# 10_-_GMAC0.net
KiCad netlist of a schematic drawn in Altium Designer
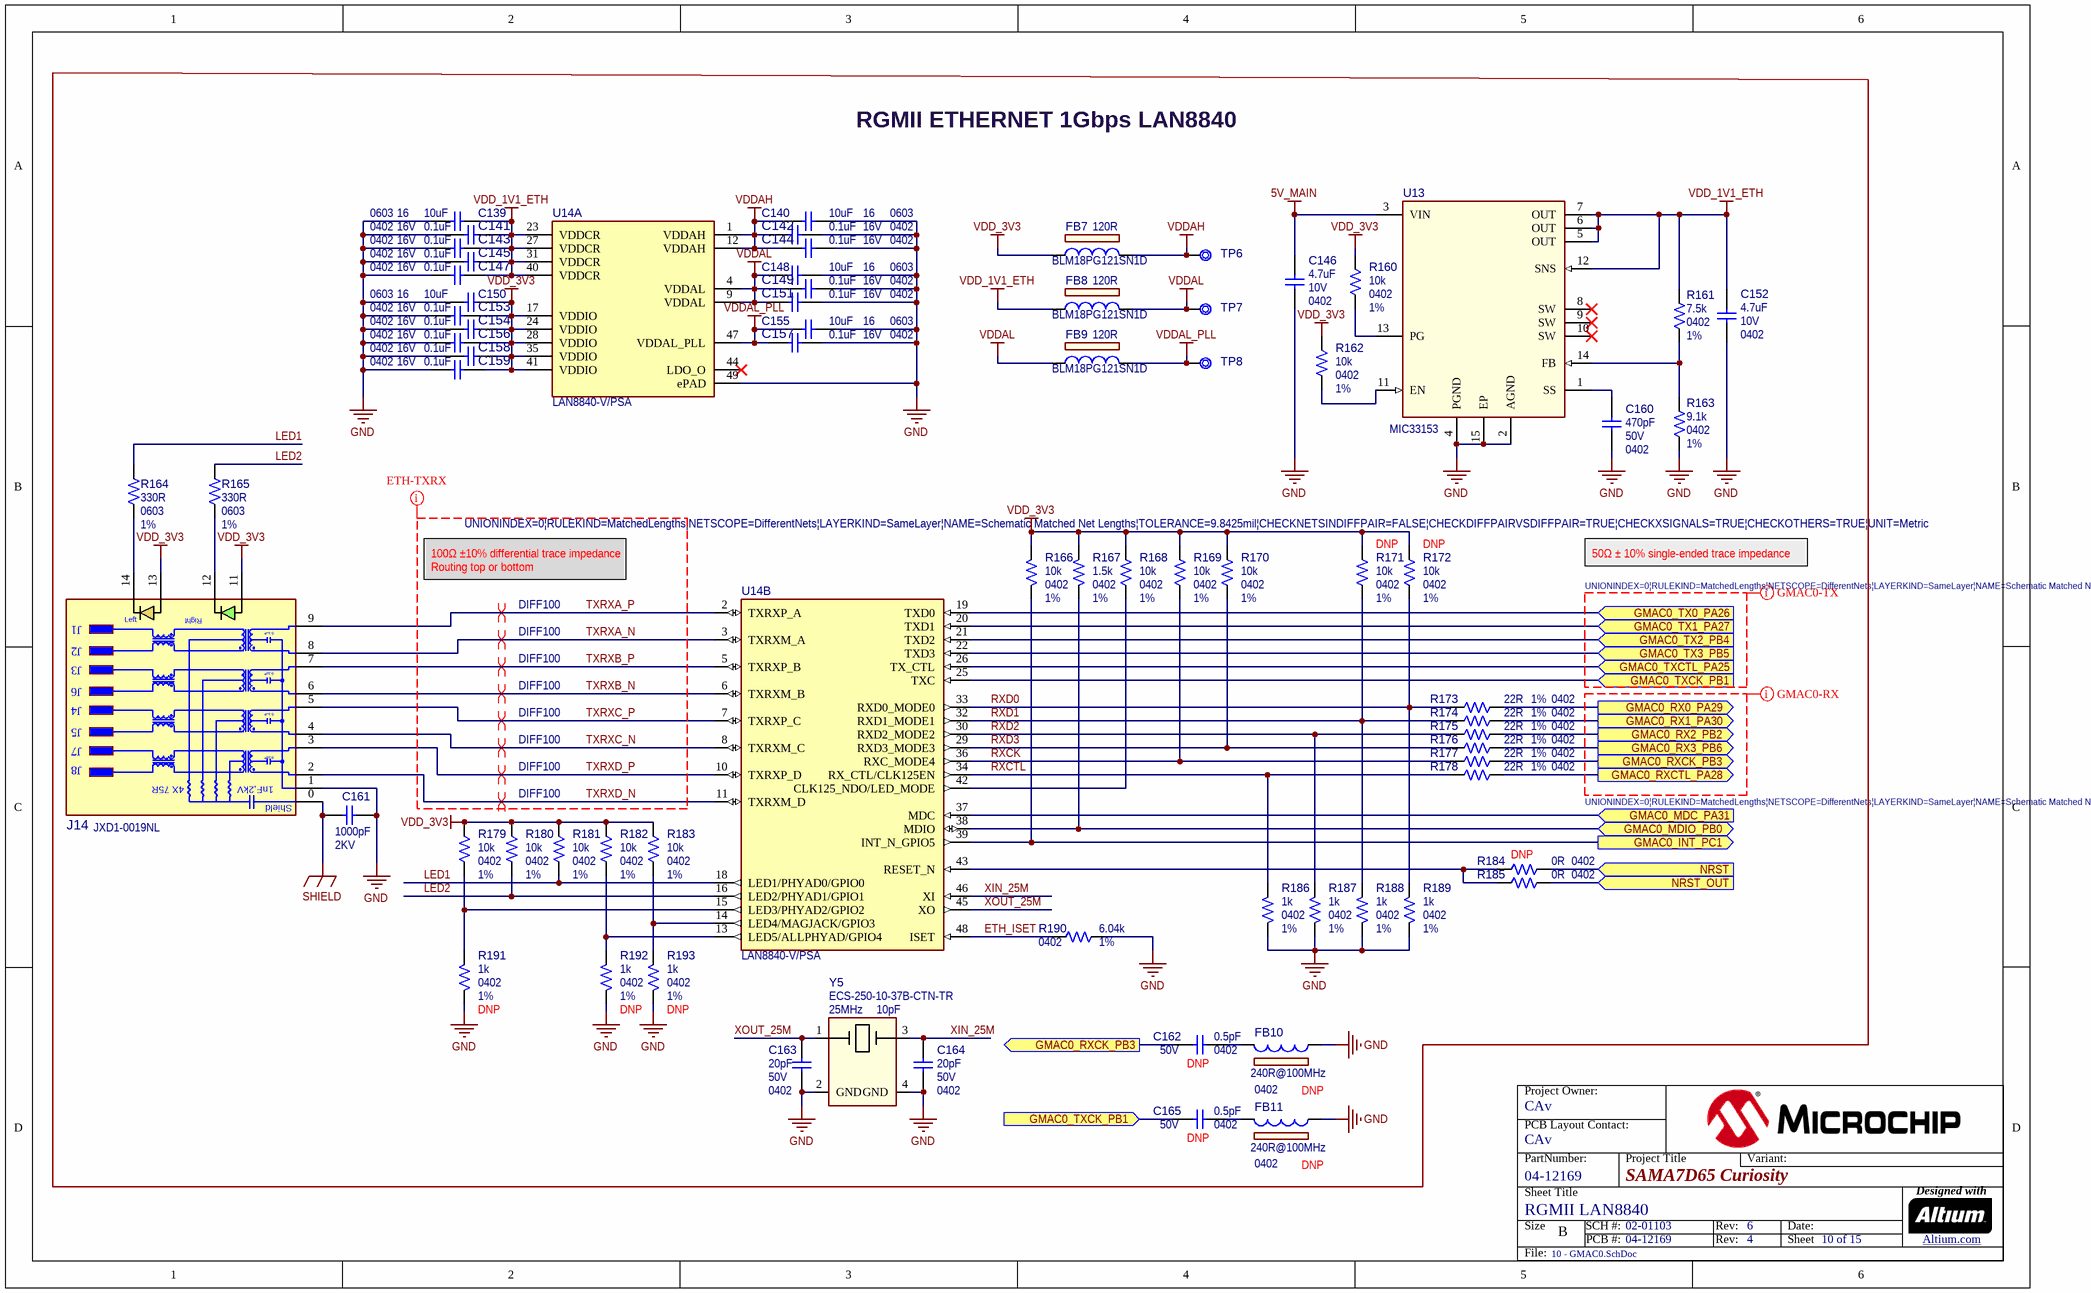
[diagram p0: 10 - GMAC0.SchDoc]

(export (version "E")
  (design (tool "Eeschema 10.0.6"))
  (components
    (comp (ref "C139")
      (value "10uF")
      (footprint "CAP_C_0603")
      (fields
        (field (name "VOLTAGE") "16")
        (field (name "PACKAGE") "0603")
        (field (name "TOLERANCE") "10%")
        (field (name "Comment") "Capacitor NP")
        (field (name "OWNER") "Sam Charles")
      )
      (libsource (lib "MCHP-CDB") (part "Capacitor NP"))
    )
    (comp (ref "C140")
      (value "10uF")
      (footprint "CAP_C_0603")
      (fields
        (field (name "VOLTAGE") "16")
        (field (name "PACKAGE") "0603")
        (field (name "TOLERANCE") "10%")
        (field (name "Comment") "Capacitor NP")
        (field (name "OWNER") "Sam Charles")
      )
      (libsource (lib "MCHP-CDB") (part "Capacitor NP"))
    )
    (comp (ref "C141")
      (value "0.1uF")
      (footprint "CAP_C_0402")
      (fields
        (field (name "VOLTAGE") "16V")
        (field (name "PACKAGE") "0402")
        (field (name "TOLERANCE") "10%")
        (field (name "Comment") "Capacitor NP")
        (field (name "OWNER") "Sompoch Loboonlert")
      )
      (libsource (lib "MCHP-CDB") (part "Capacitor NP"))
    )
    (comp (ref "C142")
      (value "0.1uF")
      (footprint "CAP_C_0402")
      (fields
        (field (name "VOLTAGE") "16V")
        (field (name "PACKAGE") "0402")
        (field (name "TOLERANCE") "10%")
        (field (name "Comment") "Capacitor NP")
        (field (name "OWNER") "Sompoch Loboonlert")
      )
      (libsource (lib "MCHP-CDB") (part "Capacitor NP"))
    )
    (comp (ref "C143")
      (value "0.1uF")
      (footprint "CAP_C_0402")
      (fields
        (field (name "VOLTAGE") "16V")
        (field (name "PACKAGE") "0402")
        (field (name "TOLERANCE") "10%")
        (field (name "Comment") "Capacitor NP")
        (field (name "OWNER") "Sompoch Loboonlert")
      )
      (libsource (lib "MCHP-CDB") (part "Capacitor NP"))
    )
    (comp (ref "C144")
      (value "0.1uF")
      (footprint "CAP_C_0402")
      (fields
        (field (name "VOLTAGE") "16V")
        (field (name "PACKAGE") "0402")
        (field (name "TOLERANCE") "10%")
        (field (name "Comment") "Capacitor NP")
        (field (name "OWNER") "Sompoch Loboonlert")
      )
      (libsource (lib "MCHP-CDB") (part "Capacitor NP"))
    )
    (comp (ref "C145")
      (value "0.1uF")
      (footprint "CAP_C_0402")
      (fields
        (field (name "VOLTAGE") "16V")
        (field (name "PACKAGE") "0402")
        (field (name "TOLERANCE") "10%")
        (field (name "Comment") "Capacitor NP")
        (field (name "OWNER") "Sompoch Loboonlert")
      )
      (libsource (lib "MCHP-CDB") (part "Capacitor NP"))
    )
    (comp (ref "C146")
      (value "4.7uF")
      (footprint "CAP_C_0402")
      (description "Capacitor")
      (fields
        (field (name "VOLTAGE") "10V")
        (field (name "PACKAGE") "0402")
        (field (name "TOLERANCE") "10%")
        (field (name "Comment") "Capacitor NP")
        (field (name "OWNER") "Jesus Aviles")
      )
      (libsource (lib "") (part "Capacitor NP_1"))
    )
    (comp (ref "C147")
      (value "0.1uF")
      (footprint "CAP_C_0402")
      (fields
        (field (name "VOLTAGE") "16V")
        (field (name "PACKAGE") "0402")
        (field (name "TOLERANCE") "10%")
        (field (name "Comment") "Capacitor NP")
        (field (name "OWNER") "Sompoch Loboonlert")
      )
      (libsource (lib "MCHP-CDB") (part "Capacitor NP"))
    )
    (comp (ref "C148")
      (value "10uF")
      (footprint "CAP_C_0603")
      (fields
        (field (name "VOLTAGE") "16")
        (field (name "PACKAGE") "0603")
        (field (name "TOLERANCE") "10%")
        (field (name "Comment") "Capacitor NP")
        (field (name "OWNER") "Sam Charles")
      )
      (libsource (lib "MCHP-CDB") (part "Capacitor NP"))
    )
    (comp (ref "C149")
      (value "0.1uF")
      (footprint "CAP_C_0402")
      (fields
        (field (name "VOLTAGE") "16V")
        (field (name "PACKAGE") "0402")
        (field (name "TOLERANCE") "10%")
        (field (name "Comment") "Capacitor NP")
        (field (name "OWNER") "Sompoch Loboonlert")
      )
      (libsource (lib "MCHP-CDB") (part "Capacitor NP"))
    )
    (comp (ref "C150")
      (value "10uF")
      (footprint "CAP_C_0603")
      (fields
        (field (name "VOLTAGE") "16")
        (field (name "PACKAGE") "0603")
        (field (name "TOLERANCE") "10%")
        (field (name "Comment") "Capacitor NP")
        (field (name "OWNER") "Sam Charles")
      )
      (libsource (lib "MCHP-CDB") (part "Capacitor NP"))
    )
    (comp (ref "C151")
      (value "0.1uF")
      (footprint "CAP_C_0402")
      (fields
        (field (name "VOLTAGE") "16V")
        (field (name "PACKAGE") "0402")
        (field (name "TOLERANCE") "10%")
        (field (name "Comment") "Capacitor NP")
        (field (name "OWNER") "Sompoch Loboonlert")
      )
      (libsource (lib "MCHP-CDB") (part "Capacitor NP"))
    )
    (comp (ref "C152")
      (value "4.7uF")
      (footprint "CAP_C_0402")
      (description "Capacitor")
      (fields
        (field (name "VOLTAGE") "10V")
        (field (name "PACKAGE") "0402")
        (field (name "TOLERANCE") "10%")
        (field (name "Comment") "Capacitor NP")
        (field (name "OWNER") "Jesus Aviles")
      )
      (libsource (lib "") (part "Capacitor NP_1"))
    )
    (comp (ref "C153")
      (value "0.1uF")
      (footprint "CAP_C_0402")
      (fields
        (field (name "VOLTAGE") "16V")
        (field (name "PACKAGE") "0402")
        (field (name "TOLERANCE") "10%")
        (field (name "Comment") "Capacitor NP")
        (field (name "OWNER") "Sompoch Loboonlert")
      )
      (libsource (lib "MCHP-CDB") (part "Capacitor NP"))
    )
    (comp (ref "C154")
      (value "0.1uF")
      (footprint "CAP_C_0402")
      (fields
        (field (name "VOLTAGE") "16V")
        (field (name "PACKAGE") "0402")
        (field (name "TOLERANCE") "10%")
        (field (name "Comment") "Capacitor NP")
        (field (name "OWNER") "Sompoch Loboonlert")
      )
      (libsource (lib "MCHP-CDB") (part "Capacitor NP"))
    )
    (comp (ref "C155")
      (value "10uF")
      (footprint "CAP_C_0603")
      (fields
        (field (name "VOLTAGE") "16")
        (field (name "PACKAGE") "0603")
        (field (name "TOLERANCE") "10%")
        (field (name "Comment") "Capacitor NP")
        (field (name "OWNER") "Sam Charles")
      )
      (libsource (lib "MCHP-CDB") (part "Capacitor NP"))
    )
    (comp (ref "C156")
      (value "0.1uF")
      (footprint "CAP_C_0402")
      (fields
        (field (name "VOLTAGE") "16V")
        (field (name "PACKAGE") "0402")
        (field (name "TOLERANCE") "10%")
        (field (name "Comment") "Capacitor NP")
        (field (name "OWNER") "Sompoch Loboonlert")
      )
      (libsource (lib "MCHP-CDB") (part "Capacitor NP"))
    )
    (comp (ref "C157")
      (value "0.1uF")
      (footprint "CAP_C_0402")
      (fields
        (field (name "VOLTAGE") "16V")
        (field (name "PACKAGE") "0402")
        (field (name "TOLERANCE") "10%")
        (field (name "Comment") "Capacitor NP")
        (field (name "OWNER") "Sompoch Loboonlert")
      )
      (libsource (lib "MCHP-CDB") (part "Capacitor NP"))
    )
    (comp (ref "C158")
      (value "0.1uF")
      (footprint "CAP_C_0402")
      (fields
        (field (name "VOLTAGE") "16V")
        (field (name "PACKAGE") "0402")
        (field (name "TOLERANCE") "10%")
        (field (name "Comment") "Capacitor NP")
        (field (name "OWNER") "Sompoch Loboonlert")
      )
      (libsource (lib "MCHP-CDB") (part "Capacitor NP"))
    )
    (comp (ref "C159")
      (value "0.1uF")
      (footprint "CAP_C_0402")
      (fields
        (field (name "VOLTAGE") "16V")
        (field (name "PACKAGE") "0402")
        (field (name "TOLERANCE") "10%")
        (field (name "Comment") "Capacitor NP")
        (field (name "OWNER") "Sompoch Loboonlert")
      )
      (libsource (lib "MCHP-CDB") (part "Capacitor NP"))
    )
    (comp (ref "C160")
      (value "470pF")
      (footprint "CAP_C_0402")
      (fields
        (field (name "VOLTAGE") "50V")
        (field (name "PACKAGE") "0402")
        (field (name "TOLERANCE") "5%")
        (field (name "Comment") "Capacitor NP")
        (field (name "OWNER") "Duane Burt")
      )
      (libsource (lib "MCHP-CDB") (part "Capacitor NP"))
    )
    (comp (ref "C161")
      (value "1000pF")
      (footprint "CAP_C_1206")
      (fields
        (field (name "VOLTAGE") "2KV")
        (field (name "Comment") "Capacitor NP")
        (field (name "OWNER") "Jamus Griego")
      )
      (libsource (lib "MCHP-CDB") (part "Capacitor NP"))
    )
    (comp (ref "C162")
      (value "0.5pF")
      (footprint "CAP_C_0402")
      (fields
        (field (name "VOLTAGE") "50V")
        (field (name "PACKAGE") "0402")
        (field (name "TOLERANCE") "0.25pF")
        (field (name "POPULATED") "DNP")
        (field (name "Comment") "Capacitor NP")
      )
      (libsource (lib "MCHP-CDB") (part "Capacitor NP"))
    )
    (comp (ref "C163")
      (value "20pF")
      (footprint "CAP_C_0402")
      (fields
        (field (name "VOLTAGE") "50V")
        (field (name "PACKAGE") "0402")
        (field (name "TOLERANCE") "5%")
        (field (name "Comment") "Capacitor NP")
      )
      (libsource (lib "MCHP-CDB") (part "Capacitor NP"))
    )
    (comp (ref "C164")
      (value "20pF")
      (footprint "CAP_C_0402")
      (fields
        (field (name "VOLTAGE") "50V")
        (field (name "PACKAGE") "0402")
        (field (name "TOLERANCE") "5%")
        (field (name "Comment") "Capacitor NP")
      )
      (libsource (lib "MCHP-CDB") (part "Capacitor NP"))
    )
    (comp (ref "C165")
      (value "0.5pF")
      (footprint "CAP_C_0402")
      (fields
        (field (name "VOLTAGE") "50V")
        (field (name "PACKAGE") "0402")
        (field (name "TOLERANCE") "0.25pF")
        (field (name "POPULATED") "DNP")
        (field (name "Comment") "Capacitor NP")
      )
      (libsource (lib "MCHP-CDB") (part "Capacitor NP"))
    )
    (comp (ref "FB7")
      (value "120R")
      (footprint "IND_C_0603")
      (fields
        (field (name "MANUFACTURER PART NUMBER 1") "BLM18PG121SN1D")
        (field (name "Comment") "Ferrite Bead")
        (field (name "OWNER") "Petnarong Chaijaroong")
      )
      (libsource (lib "") (part "Ferrite Bead_1"))
    )
    (comp (ref "FB8")
      (value "120R")
      (footprint "IND_C_0603")
      (fields
        (field (name "MANUFACTURER PART NUMBER 1") "BLM18PG121SN1D")
        (field (name "Comment") "Ferrite Bead")
        (field (name "OWNER") "Petnarong Chaijaroong")
      )
      (libsource (lib "") (part "Ferrite Bead_1"))
    )
    (comp (ref "FB9")
      (value "120R")
      (footprint "IND_C_0603")
      (fields
        (field (name "MANUFACTURER PART NUMBER 1") "BLM18PG121SN1D")
        (field (name "Comment") "Ferrite Bead")
        (field (name "OWNER") "Petnarong Chaijaroong")
      )
      (libsource (lib "") (part "Ferrite Bead_1"))
    )
    (comp (ref "FB10")
      (value "240R@100MHz")
      (footprint "IND_C_0402")
      (fields
        (field (name "PACKAGE") "0402")
        (field (name "POPULATED") "DNP")
        (field (name "Comment") "Ferrite Bead")
        (field (name "OWNER") "Joerg Buehrer")
      )
      (libsource (lib "MCHP-CDB") (part "Ferrite Bead"))
    )
    (comp (ref "FB11")
      (value "240R@100MHz")
      (footprint "IND_C_0402")
      (fields
        (field (name "PACKAGE") "0402")
        (field (name "POPULATED") "DNP")
        (field (name "Comment") "Ferrite Bead")
        (field (name "OWNER") "Joerg Buehrer")
      )
      (libsource (lib "MCHP-CDB") (part "Ferrite Bead"))
    )
    (comp (ref "J14")
      (value "CON_RJ-45_TH_RA_PULSE_JXD1-0019NL")
      (footprint "CON_RJ-45_TH_RA_PULSE_JXD1-0019NL")
      (fields
        (field (name "MANUFACTURER PART NUMBER 1") "JXD1-0019NL")
        (field (name "OWNER") "Ciprian Abramov")
      )
      (libsource (lib "MCHP-CDB") (part "CON_RJ-45_TH_RA_PULSE_JXD1-0019NL"))
    )
    (comp (ref "R160")
      (value "10k")
      (footprint "RES_C_0402")
      (description "Resistor")
      (fields
        (field (name "PACKAGE") "0402")
        (field (name "TOLERANCE") "1%")
        (field (name "VOLTAGE") "50V")
        (field (name "POWER") "1/10W")
        (field (name "OWNER") "Brent Lanphear")
      )
      (libsource (lib "MCHP-CDB") (part "Resistor"))
    )
    (comp (ref "R161")
      (value "7.5k")
      (footprint "RES_C_0402")
      (description "Resistor")
      (fields
        (field (name "PACKAGE") "0402")
        (field (name "TOLERANCE") "1%")
        (field (name "POWER") "1/16W")
        (field (name "OWNER") "Stephen Humberd")
      )
      (libsource (lib "MCHP-CDB") (part "Resistor"))
    )
    (comp (ref "R162")
      (value "10k")
      (footprint "RES_C_0402")
      (description "Resistor")
      (fields
        (field (name "PACKAGE") "0402")
        (field (name "TOLERANCE") "1%")
        (field (name "VOLTAGE") "50V")
        (field (name "POWER") "1/10W")
        (field (name "OWNER") "Brent Lanphear")
      )
      (libsource (lib "MCHP-CDB") (part "Resistor"))
    )
    (comp (ref "R163")
      (value "9.1k")
      (footprint "RES_C_0402")
      (description "Resistor")
      (fields
        (field (name "PACKAGE") "0402")
        (field (name "TOLERANCE") "1%")
        (field (name "VOLTAGE") "50V")
        (field (name "POWER") "1/10W")
      )
      (libsource (lib "MCHP-CDB") (part "Resistor"))
    )
    (comp (ref "R164")
      (value "330R")
      (footprint "RES_C_0603")
      (description "Resistor")
      (fields
        (field (name "PACKAGE") "0603")
        (field (name "TOLERANCE") "1%")
        (field (name "VOLTAGE") "75V")
        (field (name "POWER") "1/10W")
      )
      (libsource (lib "MCHP-CDB") (part "Resistor"))
    )
    (comp (ref "R165")
      (value "330R")
      (footprint "RES_C_0603")
      (description "Resistor")
      (fields
        (field (name "PACKAGE") "0603")
        (field (name "TOLERANCE") "1%")
        (field (name "VOLTAGE") "75V")
        (field (name "POWER") "1/10W")
      )
      (libsource (lib "MCHP-CDB") (part "Resistor"))
    )
    (comp (ref "R166")
      (value "10k")
      (footprint "RES_C_0402")
      (description "Resistor")
      (fields
        (field (name "PACKAGE") "0402")
        (field (name "TOLERANCE") "1%")
        (field (name "VOLTAGE") "50V")
        (field (name "POWER") "1/10W")
        (field (name "OWNER") "Brent Lanphear")
      )
      (libsource (lib "MCHP-CDB") (part "Resistor"))
    )
    (comp (ref "R167")
      (value "1.5k")
      (footprint "RES_C_0402")
      (description "Resistor")
      (fields
        (field (name "PACKAGE") "0402")
        (field (name "TOLERANCE") "1%")
        (field (name "POWER") "1/10W")
        (field (name "OWNER") "Gabor Bihari")
      )
      (libsource (lib "MCHP-CDB") (part "Resistor"))
    )
    (comp (ref "R168")
      (value "10k")
      (footprint "RES_C_0402")
      (description "Resistor")
      (fields
        (field (name "PACKAGE") "0402")
        (field (name "TOLERANCE") "1%")
        (field (name "VOLTAGE") "50V")
        (field (name "POWER") "1/10W")
        (field (name "OWNER") "Brent Lanphear")
      )
      (libsource (lib "MCHP-CDB") (part "Resistor"))
    )
    (comp (ref "R169")
      (value "10k")
      (footprint "RES_C_0402")
      (description "Resistor")
      (fields
        (field (name "PACKAGE") "0402")
        (field (name "TOLERANCE") "1%")
        (field (name "VOLTAGE") "50V")
        (field (name "POWER") "1/10W")
        (field (name "OWNER") "Brent Lanphear")
      )
      (libsource (lib "MCHP-CDB") (part "Resistor"))
    )
    (comp (ref "R170")
      (value "10k")
      (footprint "RES_C_0402")
      (description "Resistor")
      (fields
        (field (name "PACKAGE") "0402")
        (field (name "TOLERANCE") "1%")
        (field (name "VOLTAGE") "50V")
        (field (name "POWER") "1/10W")
        (field (name "OWNER") "Brent Lanphear")
      )
      (libsource (lib "MCHP-CDB") (part "Resistor"))
    )
    (comp (ref "R171")
      (value "10k")
      (footprint "RES_C_0402")
      (description "Resistor")
      (fields
        (field (name "PACKAGE") "0402")
        (field (name "TOLERANCE") "1%")
        (field (name "VOLTAGE") "50V")
        (field (name "POWER") "1/10W")
        (field (name "POPULATED") "DNP")
        (field (name "OWNER") "Brent Lanphear")
      )
      (libsource (lib "MCHP-CDB") (part "Resistor"))
    )
    (comp (ref "R172")
      (value "10k")
      (footprint "RES_C_0402")
      (description "Resistor")
      (fields
        (field (name "PACKAGE") "0402")
        (field (name "TOLERANCE") "1%")
        (field (name "VOLTAGE") "50V")
        (field (name "POWER") "1/10W")
        (field (name "POPULATED") "DNP")
        (field (name "OWNER") "Brent Lanphear")
      )
      (libsource (lib "MCHP-CDB") (part "Resistor"))
    )
    (comp (ref "R173")
      (value "22R")
      (footprint "RES_C_0402")
      (description "Resistor")
      (fields
        (field (name "PACKAGE") "0402")
        (field (name "TOLERANCE") "1%")
        (field (name "POWER") "1/10W")
        (field (name "OWNER") "Mike Ragsdale")
      )
      (libsource (lib "MCHP-CDB") (part "Resistor"))
    )
    (comp (ref "R174")
      (value "22R")
      (footprint "RES_C_0402")
      (description "Resistor")
      (fields
        (field (name "PACKAGE") "0402")
        (field (name "TOLERANCE") "1%")
        (field (name "POWER") "1/10W")
        (field (name "OWNER") "Mike Ragsdale")
      )
      (libsource (lib "MCHP-CDB") (part "Resistor"))
    )
    (comp (ref "R175")
      (value "22R")
      (footprint "RES_C_0402")
      (description "Resistor")
      (fields
        (field (name "PACKAGE") "0402")
        (field (name "TOLERANCE") "1%")
        (field (name "POWER") "1/10W")
        (field (name "OWNER") "Mike Ragsdale")
      )
      (libsource (lib "MCHP-CDB") (part "Resistor"))
    )
    (comp (ref "R176")
      (value "22R")
      (footprint "RES_C_0402")
      (description "Resistor")
      (fields
        (field (name "PACKAGE") "0402")
        (field (name "TOLERANCE") "1%")
        (field (name "POWER") "1/10W")
        (field (name "OWNER") "Mike Ragsdale")
      )
      (libsource (lib "MCHP-CDB") (part "Resistor"))
    )
    (comp (ref "R177")
      (value "22R")
      (footprint "RES_C_0402")
      (description "Resistor")
      (fields
        (field (name "PACKAGE") "0402")
        (field (name "TOLERANCE") "1%")
        (field (name "POWER") "1/10W")
        (field (name "OWNER") "Mike Ragsdale")
      )
      (libsource (lib "MCHP-CDB") (part "Resistor"))
    )
    (comp (ref "R178")
      (value "22R")
      (footprint "RES_C_0402")
      (description "Resistor")
      (fields
        (field (name "PACKAGE") "0402")
        (field (name "TOLERANCE") "1%")
        (field (name "POWER") "1/10W")
        (field (name "OWNER") "Mike Ragsdale")
      )
      (libsource (lib "MCHP-CDB") (part "Resistor"))
    )
    (comp (ref "R179")
      (value "10k")
      (footprint "RES_C_0402")
      (description "Resistor")
      (fields
        (field (name "PACKAGE") "0402")
        (field (name "TOLERANCE") "1%")
        (field (name "VOLTAGE") "50V")
        (field (name "POWER") "1/10W")
        (field (name "OWNER") "Brent Lanphear")
      )
      (libsource (lib "MCHP-CDB") (part "Resistor"))
    )
    (comp (ref "R180")
      (value "10k")
      (footprint "RES_C_0402")
      (description "Resistor")
      (fields
        (field (name "PACKAGE") "0402")
        (field (name "TOLERANCE") "1%")
        (field (name "VOLTAGE") "50V")
        (field (name "POWER") "1/10W")
        (field (name "OWNER") "Brent Lanphear")
      )
      (libsource (lib "MCHP-CDB") (part "Resistor"))
    )
    (comp (ref "R181")
      (value "10k")
      (footprint "RES_C_0402")
      (description "Resistor")
      (fields
        (field (name "PACKAGE") "0402")
        (field (name "TOLERANCE") "1%")
        (field (name "VOLTAGE") "50V")
        (field (name "POWER") "1/10W")
        (field (name "OWNER") "Brent Lanphear")
      )
      (libsource (lib "MCHP-CDB") (part "Resistor"))
    )
    (comp (ref "R182")
      (value "10k")
      (footprint "RES_C_0402")
      (description "Resistor")
      (fields
        (field (name "PACKAGE") "0402")
        (field (name "TOLERANCE") "1%")
        (field (name "VOLTAGE") "50V")
        (field (name "POWER") "1/10W")
        (field (name "OWNER") "Brent Lanphear")
      )
      (libsource (lib "MCHP-CDB") (part "Resistor"))
    )
    (comp (ref "R183")
      (value "10k")
      (footprint "RES_C_0402")
      (description "Resistor")
      (fields
        (field (name "PACKAGE") "0402")
        (field (name "TOLERANCE") "1%")
        (field (name "VOLTAGE") "50V")
        (field (name "POWER") "1/10W")
        (field (name "OWNER") "Brent Lanphear")
      )
      (libsource (lib "MCHP-CDB") (part "Resistor"))
    )
    (comp (ref "R184")
      (value "0R")
      (footprint "RES_C_0402")
      (description "Resistor")
      (fields
        (field (name "PACKAGE") "0402")
        (field (name "POWER") "1/16W")
        (field (name "POPULATED") "DNP")
        (field (name "OWNER") "Sompoch Loboonlert")
      )
      (libsource (lib "MCHP-CDB") (part "Resistor"))
    )
    (comp (ref "R185")
      (value "0R")
      (footprint "RES_C_0402")
      (description "Resistor")
      (fields
        (field (name "PACKAGE") "0402")
        (field (name "POWER") "1/16W")
        (field (name "OWNER") "Sompoch Loboonlert")
      )
      (libsource (lib "MCHP-CDB") (part "Resistor"))
    )
    (comp (ref "R186")
      (value "1k")
      (footprint "RES_C_0402")
      (description "Resistor")
      (fields
        (field (name "PACKAGE") "0402")
        (field (name "TOLERANCE") "1%")
        (field (name "VOLTAGE") "50V")
        (field (name "POWER") "1/10W")
        (field (name "OWNER") "Tad Ahlvers")
      )
      (libsource (lib "MCHP-CDB") (part "Resistor"))
    )
    (comp (ref "R187")
      (value "1k")
      (footprint "RES_C_0402")
      (description "Resistor")
      (fields
        (field (name "PACKAGE") "0402")
        (field (name "TOLERANCE") "1%")
        (field (name "VOLTAGE") "50V")
        (field (name "POWER") "1/10W")
        (field (name "OWNER") "Tad Ahlvers")
      )
      (libsource (lib "MCHP-CDB") (part "Resistor"))
    )
    (comp (ref "R188")
      (value "1k")
      (footprint "RES_C_0402")
      (description "Resistor")
      (fields
        (field (name "PACKAGE") "0402")
        (field (name "TOLERANCE") "1%")
        (field (name "VOLTAGE") "50V")
        (field (name "POWER") "1/10W")
        (field (name "OWNER") "Tad Ahlvers")
      )
      (libsource (lib "MCHP-CDB") (part "Resistor"))
    )
    (comp (ref "R189")
      (value "1k")
      (footprint "RES_C_0402")
      (description "Resistor")
      (fields
        (field (name "PACKAGE") "0402")
        (field (name "TOLERANCE") "1%")
        (field (name "VOLTAGE") "50V")
        (field (name "POWER") "1/10W")
        (field (name "OWNER") "Tad Ahlvers")
      )
      (libsource (lib "MCHP-CDB") (part "Resistor"))
    )
    (comp (ref "R190")
      (value "6.04k")
      (footprint "RES_C_0402")
      (description "Resistor")
      (fields
        (field (name "PACKAGE") "0402")
        (field (name "TOLERANCE") "1%")
        (field (name "POWER") "1/10W")
        (field (name "OWNER") "Steve Dziaba")
      )
      (libsource (lib "MCHP-CDB") (part "Resistor"))
    )
    (comp (ref "R191")
      (value "1k")
      (footprint "RES_C_0402")
      (description "Resistor")
      (fields
        (field (name "PACKAGE") "0402")
        (field (name "TOLERANCE") "1%")
        (field (name "VOLTAGE") "50V")
        (field (name "POWER") "1/10W")
        (field (name "POPULATED") "DNP")
        (field (name "OWNER") "Tad Ahlvers")
      )
      (libsource (lib "MCHP-CDB") (part "Resistor"))
    )
    (comp (ref "R192")
      (value "1k")
      (footprint "RES_C_0402")
      (description "Resistor")
      (fields
        (field (name "PACKAGE") "0402")
        (field (name "TOLERANCE") "1%")
        (field (name "VOLTAGE") "50V")
        (field (name "POWER") "1/10W")
        (field (name "POPULATED") "DNP")
        (field (name "OWNER") "Tad Ahlvers")
      )
      (libsource (lib "MCHP-CDB") (part "Resistor"))
    )
    (comp (ref "R193")
      (value "1k")
      (footprint "RES_C_0402")
      (description "Resistor")
      (fields
        (field (name "PACKAGE") "0402")
        (field (name "TOLERANCE") "1%")
        (field (name "VOLTAGE") "50V")
        (field (name "POWER") "1/10W")
        (field (name "POPULATED") "DNP")
        (field (name "OWNER") "Tad Ahlvers")
      )
      (libsource (lib "MCHP-CDB") (part "Resistor"))
    )
    (comp (ref "TP6")
      (value "Test Point No BOM")
      (footprint "TP_1mm_SMD")
      (description "Test Point")
      (fields (field (name "OWNER") "Cristian Papuc"))
      (libsource (lib "MCHP-CDB") (part "Test Point No BOM"))
    )
    (comp (ref "TP7")
      (value "Test Point No BOM")
      (footprint "TP_1mm_SMD")
      (description "Test Point")
      (fields (field (name "OWNER") "Cristian Papuc"))
      (libsource (lib "MCHP-CDB") (part "Test Point No BOM"))
    )
    (comp (ref "TP8")
      (value "Test Point No BOM")
      (footprint "TP_1mm_SMD")
      (description "Test Point")
      (fields (field (name "OWNER") "Cristian Papuc"))
      (libsource (lib "MCHP-CDB") (part "Test Point No BOM"))
    )
    (comp (ref "U13")
      (value "MIC33153")
      (footprint "VFDFN-14_3X3.5_MIC33153")
      (fields (field (name "Comment") "MIC33153 VFDFN-14") (field (name "OWNER") "Razvan Cristescu"))
      (libsource (lib "MCHP-CDB") (part "MIC33153 VFDFN-14"))
    )
    (comp (ref "U14")
      (value "LAN8840-V/PSA")
      (footprint "QFN-48_7x7_EP5.1x5.1")
      (fields (field (name "Comment") "LAN8840_QFN-48") (field (name "OWNER") "Sam Charles"))
      (libsource (lib "MCHP-CDB") (part "LAN8840_QFN-48"))
    )
    (comp (ref "Y5")
      (value "25MHz")
      (footprint "CRYSTAL_L2.0W1.6H0.5_FA-128")
      (fields
        (field (name "TOLERANCE") "10ppm")
        (field (name "LOAD CAPACITANCE") "10pF")
        (field (name "MANUFACTURER PART NUMBER 1") "ECS-250-10-37B-CTN-TR")
        (field (name "Comment") "Crystal 4 Pins")
        (field (name "OWNER") "Ciprian Abramov")
      )
      (libsource (lib "MCHP-CDB") (part "Crystal 4 Pins"))
    )
  )
  (nets
    (net (code "1") (name "/ETH_ISET") (class "Default")
      (node (ref "R190") (pin "1") (pinfunction "1_1") (pintype "passive"))
      (node (ref "U14") (pin "48") (pinfunction "ISET_48") (pintype "input"))
    )
    (net (code "2") (name "/GMAC0_INT_PC1") (class "Default")
      (node (ref "R166") (pin "1") (pinfunction "1_1") (pintype "passive"))
      (node (ref "U14") (pin "39") (pinfunction "INT_N_GPIO5_39") (pintype "output"))
    )
    (net (code "3") (name "/GMAC0_MDC_PA31") (class "Default")
      (node (ref "U14") (pin "37") (pinfunction "MDC_37") (pintype "input"))
    )
    (net (code "4") (name "/GMAC0_MDIO_PB0") (class "Default")
      (node (ref "R167") (pin "1") (pinfunction "1_1") (pintype "passive"))
      (node (ref "U14") (pin "38") (pinfunction "MDIO_38") (pintype "bidirectional"))
    )
    (net (code "5") (name "/GMAC0_RX0_PA29") (class "Default")
      (node (ref "R173") (pin "2") (pinfunction "2_2") (pintype "passive"))
    )
    (net (code "6") (name "/GMAC0_RX1_PA30") (class "Default")
      (node (ref "R174") (pin "2") (pinfunction "2_2") (pintype "passive"))
    )
    (net (code "7") (name "/GMAC0_RX2_PB2") (class "Default")
      (node (ref "R175") (pin "2") (pinfunction "2_2") (pintype "passive"))
    )
    (net (code "8") (name "/GMAC0_RX3_PB6") (class "Default")
      (node (ref "R176") (pin "2") (pinfunction "2_2") (pintype "passive"))
    )
    (net (code "9") (name "/GMAC0_RXCK_PB3") (class "Default")
      (node (ref "C162") (pin "2") (pinfunction "2_2") (pintype "passive"))
      (node (ref "R177") (pin "2") (pinfunction "2_2") (pintype "passive"))
    )
    (net (code "10") (name "/GMAC0_RXCTL_PA28") (class "Default")
      (node (ref "R178") (pin "2") (pinfunction "2_2") (pintype "passive"))
    )
    (net (code "11") (name "/GMAC0_TX0_PA26") (class "Default")
      (node (ref "U14") (pin "19") (pinfunction "TXD0_19") (pintype "input"))
    )
    (net (code "12") (name "/GMAC0_TX1_PA27") (class "Default")
      (node (ref "U14") (pin "20") (pinfunction "TXD1_20") (pintype "input"))
    )
    (net (code "13") (name "/GMAC0_TX2_PB4") (class "Default")
      (node (ref "U14") (pin "21") (pinfunction "TXD2_21") (pintype "input"))
    )
    (net (code "14") (name "/GMAC0_TX3_PB5") (class "Default")
      (node (ref "U14") (pin "22") (pinfunction "TXD3_22") (pintype "input"))
    )
    (net (code "15") (name "/GMAC0_TXCK_PB1") (class "Default")
      (node (ref "C165") (pin "2") (pinfunction "2_2") (pintype "passive"))
      (node (ref "U14") (pin "25") (pinfunction "TXC_25") (pintype "input"))
    )
    (net (code "16") (name "/GMAC0_TXCTL_PA25") (class "Default")
      (node (ref "U14") (pin "26") (pinfunction "TX_CTL_26") (pintype "input"))
    )
    (net (code "17") (name "/LED1") (class "Default")
      (node (ref "R164") (pin "2") (pinfunction "2_2") (pintype "passive"))
      (node (ref "R181") (pin "1") (pinfunction "1_1") (pintype "passive"))
      (node (ref "U14") (pin "18") (pinfunction "LED1/PHYAD0/GPIO0_18") (pintype "output"))
    )
    (net (code "18") (name "/LED2") (class "Default")
      (node (ref "R165") (pin "2") (pinfunction "2_2") (pintype "passive"))
      (node (ref "R180") (pin "1") (pinfunction "1_1") (pintype "passive"))
      (node (ref "U14") (pin "16") (pinfunction "LED2/PHYAD1/GPIO1_16") (pintype "output"))
    )
    (net (code "19") (name "/NRST") (class "Default")
      (node (ref "R184") (pin "2") (pinfunction "2_2") (pintype "passive"))
    )
    (net (code "20") (name "/NRST_OUT") (class "Default")
      (node (ref "R185") (pin "2") (pinfunction "2_2") (pintype "passive"))
    )
    (net (code "21") (name "/RXCK") (class "Default")
      (node (ref "R169") (pin "1") (pinfunction "1_1") (pintype "passive"))
      (node (ref "R177") (pin "1") (pinfunction "1_1") (pintype "passive"))
      (node (ref "U14") (pin "36") (pinfunction "RXC_MODE4_36") (pintype "output"))
    )
    (net (code "22") (name "/RXCTL") (class "Default")
      (node (ref "R178") (pin "1") (pinfunction "1_1") (pintype "passive"))
      (node (ref "R186") (pin "2") (pinfunction "2_2") (pintype "passive"))
      (node (ref "U14") (pin "34") (pinfunction "RX_CTL/CLK125EN_34") (pintype "output"))
    )
    (net (code "23") (name "/RXD0") (class "Default")
      (node (ref "R172") (pin "1") (pinfunction "1_1") (pintype "passive"))
      (node (ref "R173") (pin "1") (pinfunction "1_1") (pintype "passive"))
      (node (ref "R189") (pin "2") (pinfunction "2_2") (pintype "passive"))
      (node (ref "U14") (pin "33") (pinfunction "RXD0_MODE0_33") (pintype "output"))
    )
    (net (code "24") (name "/RXD1") (class "Default")
      (node (ref "R171") (pin "1") (pinfunction "1_1") (pintype "passive"))
      (node (ref "R174") (pin "1") (pinfunction "1_1") (pintype "passive"))
      (node (ref "R188") (pin "2") (pinfunction "2_2") (pintype "passive"))
      (node (ref "U14") (pin "32") (pinfunction "RXD1_MODE1_32") (pintype "output"))
    )
    (net (code "25") (name "/RXD2") (class "Default")
      (node (ref "R175") (pin "1") (pinfunction "1_1") (pintype "passive"))
      (node (ref "R187") (pin "2") (pinfunction "2_2") (pintype "passive"))
      (node (ref "U14") (pin "30") (pinfunction "RXD2_MODE2_30") (pintype "output"))
    )
    (net (code "26") (name "/RXD3") (class "Default")
      (node (ref "R170") (pin "1") (pinfunction "1_1") (pintype "passive"))
      (node (ref "R176") (pin "1") (pinfunction "1_1") (pintype "passive"))
      (node (ref "U14") (pin "29") (pinfunction "RXD3_MODE3_29") (pintype "output"))
    )
    (net (code "27") (name "/TXRXA_N") (class "Default")
      (node (ref "J14") (pin "8") (pintype "passive"))
      (node (ref "U14") (pin "3") (pinfunction "TXRXM_A_3") (pintype "bidirectional"))
    )
    (net (code "28") (name "/TXRXA_P") (class "Default")
      (node (ref "J14") (pin "9") (pintype "passive"))
      (node (ref "U14") (pin "2") (pinfunction "TXRXP_A_2") (pintype "bidirectional"))
    )
    (net (code "29") (name "/TXRXB_N") (class "Default")
      (node (ref "J14") (pin "6") (pintype "passive"))
      (node (ref "U14") (pin "6") (pinfunction "TXRXM_B_6") (pintype "bidirectional"))
    )
    (net (code "30") (name "/TXRXB_P") (class "Default")
      (node (ref "J14") (pin "7") (pintype "passive"))
      (node (ref "U14") (pin "5") (pinfunction "TXRXP_B_5") (pintype "bidirectional"))
    )
    (net (code "31") (name "/TXRXC_N") (class "Default")
      (node (ref "J14") (pin "4") (pintype "passive"))
      (node (ref "U14") (pin "8") (pinfunction "TXRXM_C_8") (pintype "bidirectional"))
    )
    (net (code "32") (name "/TXRXC_P") (class "Default")
      (node (ref "J14") (pin "5") (pintype "passive"))
      (node (ref "U14") (pin "7") (pinfunction "TXRXP_C_7") (pintype "bidirectional"))
    )
    (net (code "33") (name "/TXRXD_N") (class "Default")
      (node (ref "J14") (pin "2") (pintype "passive"))
      (node (ref "U14") (pin "11") (pinfunction "TXRXM_D_11") (pintype "bidirectional"))
    )
    (net (code "34") (name "/TXRXD_P") (class "Default")
      (node (ref "J14") (pin "3") (pintype "passive"))
      (node (ref "U14") (pin "10") (pinfunction "TXRXP_D_10") (pintype "bidirectional"))
    )
    (net (code "35") (name "/XIN_25M") (class "Default")
      (node (ref "C164") (pin "2") (pinfunction "2_2") (pintype "passive"))
      (node (ref "U14") (pin "46") (pinfunction "XI_46") (pintype "input"))
      (node (ref "Y5") (pin "3") (pinfunction "Osc2_3") (pintype "passive"))
    )
    (net (code "36") (name "/XOUT_25M") (class "Default")
      (node (ref "C163") (pin "2") (pinfunction "2_2") (pintype "passive"))
      (node (ref "U14") (pin "45") (pinfunction "XO_45") (pintype "output"))
      (node (ref "Y5") (pin "1") (pinfunction "Osc1_1") (pintype "passive"))
    )
    (net (code "37") (name "5V_MAIN") (class "Default")
      (node (ref "C146") (pin "2") (pinfunction "2_2") (pintype "passive"))
      (node (ref "U13") (pin "3") (pinfunction "VIN_3") (pintype "power_in"))
    )
    (net (code "38") (name "GND") (class "Default")
      (node (ref "C139") (pin "2") (pinfunction "2_2") (pintype "passive"))
      (node (ref "C140") (pin "2") (pinfunction "2_2") (pintype "passive"))
      (node (ref "C141") (pin "2") (pinfunction "2_2") (pintype "passive"))
      (node (ref "C142") (pin "2") (pinfunction "2_2") (pintype "passive"))
      (node (ref "C143") (pin "2") (pinfunction "2_2") (pintype "passive"))
      (node (ref "C144") (pin "2") (pinfunction "2_2") (pintype "passive"))
      (node (ref "C145") (pin "2") (pinfunction "2_2") (pintype "passive"))
      (node (ref "C146") (pin "1") (pinfunction "1_1") (pintype "passive"))
      (node (ref "C147") (pin "2") (pinfunction "2_2") (pintype "passive"))
      (node (ref "C148") (pin "2") (pinfunction "2_2") (pintype "passive"))
      (node (ref "C149") (pin "2") (pinfunction "2_2") (pintype "passive"))
      (node (ref "C150") (pin "2") (pinfunction "2_2") (pintype "passive"))
      (node (ref "C151") (pin "2") (pinfunction "2_2") (pintype "passive"))
      (node (ref "C152") (pin "1") (pinfunction "1_1") (pintype "passive"))
      (node (ref "C153") (pin "2") (pinfunction "2_2") (pintype "passive"))
      (node (ref "C154") (pin "2") (pinfunction "2_2") (pintype "passive"))
      (node (ref "C155") (pin "2") (pinfunction "2_2") (pintype "passive"))
      (node (ref "C156") (pin "2") (pinfunction "2_2") (pintype "passive"))
      (node (ref "C157") (pin "2") (pinfunction "2_2") (pintype "passive"))
      (node (ref "C158") (pin "2") (pinfunction "2_2") (pintype "passive"))
      (node (ref "C159") (pin "2") (pinfunction "2_2") (pintype "passive"))
      (node (ref "C160") (pin "1") (pinfunction "1_1") (pintype "passive"))
      (node (ref "C161") (pin "1") (pinfunction "1_1") (pintype "passive"))
      (node (ref "C163") (pin "1") (pinfunction "1_1") (pintype "passive"))
      (node (ref "C164") (pin "1") (pinfunction "1_1") (pintype "passive"))
      (node (ref "FB10") (pin "1") (pinfunction "1_1") (pintype "passive"))
      (node (ref "FB11") (pin "1") (pinfunction "1_1") (pintype "passive"))
      (node (ref "J14") (pin "1") (pintype "passive"))
      (node (ref "R163") (pin "1") (pinfunction "1_1") (pintype "passive"))
      (node (ref "R186") (pin "1") (pinfunction "1_1") (pintype "passive"))
      (node (ref "R187") (pin "1") (pinfunction "1_1") (pintype "passive"))
      (node (ref "R188") (pin "1") (pinfunction "1_1") (pintype "passive"))
      (node (ref "R189") (pin "1") (pinfunction "1_1") (pintype "passive"))
      (node (ref "R190") (pin "2") (pinfunction "2_2") (pintype "passive"))
      (node (ref "R191") (pin "1") (pinfunction "1_1") (pintype "passive"))
      (node (ref "R192") (pin "1") (pinfunction "1_1") (pintype "passive"))
      (node (ref "R193") (pin "1") (pinfunction "1_1") (pintype "passive"))
      (node (ref "U13") (pin "15") (pinfunction "EP_15") (pintype "power_in"))
      (node (ref "U13") (pin "2") (pinfunction "AGND_2") (pintype "power_in"))
      (node (ref "U13") (pin "4") (pinfunction "PGND_4") (pintype "power_in"))
      (node (ref "U14") (pin "49") (pinfunction "ePAD_49") (pintype "power_in"))
      (node (ref "Y5") (pin "2") (pinfunction "GND_2") (pintype "passive"))
      (node (ref "Y5") (pin "4") (pinfunction "GND_4") (pintype "passive"))
    )
    (net (code "39") (name "Net-(C162-Pad1)") (class "Default")
      (node (ref "C162") (pin "1") (pinfunction "1_1") (pintype "passive"))
      (node (ref "FB10") (pin "2") (pinfunction "2_2") (pintype "passive"))
    )
    (net (code "40") (name "Net-(C165-Pad1)") (class "Default")
      (node (ref "C165") (pin "1") (pinfunction "1_1") (pintype "passive"))
      (node (ref "FB11") (pin "2") (pinfunction "2_2") (pintype "passive"))
    )
    (net (code "41") (name "Net-(J14-Pad12)") (class "Default")
      (node (ref "J14") (pin "12") (pintype "passive"))
      (node (ref "R165") (pin "1") (pinfunction "1_1") (pintype "passive"))
    )
    (net (code "42") (name "Net-(J14-Pad14)") (class "Default")
      (node (ref "J14") (pin "14") (pintype "passive"))
      (node (ref "R164") (pin "1") (pinfunction "1_1") (pintype "passive"))
    )
    (net (code "43") (name "Net-(U13-EN)") (class "Default")
      (node (ref "R162") (pin "1") (pinfunction "1_1") (pintype "passive"))
      (node (ref "U13") (pin "11") (pinfunction "EN_11") (pintype "input"))
    )
    (net (code "44") (name "Net-(U13-FB)") (class "Default")
      (node (ref "R161") (pin "1") (pinfunction "1_1") (pintype "passive"))
      (node (ref "R163") (pin "2") (pinfunction "2_2") (pintype "passive"))
      (node (ref "U13") (pin "14") (pinfunction "FB_14") (pintype "input"))
    )
    (net (code "45") (name "Net-(U13-PG)") (class "Default")
      (node (ref "R160") (pin "1") (pinfunction "1_1") (pintype "passive"))
      (node (ref "U13") (pin "13") (pinfunction "PG_13") (pintype "open_collector"))
    )
    (net (code "46") (name "Net-(U13-SS)") (class "Default")
      (node (ref "C160") (pin "2") (pinfunction "2_2") (pintype "passive"))
      (node (ref "U13") (pin "1") (pinfunction "SS_1") (pintype "power_in"))
    )
    (net (code "47") (name "Net-(U14B-CLK125_NDO{slash}LED_MODE)") (class "Default")
      (node (ref "R168") (pin "1") (pinfunction "1_1") (pintype "passive"))
      (node (ref "U14") (pin "42") (pinfunction "CLK125_NDO/LED_MODE_42") (pintype "output"))
    )
    (net (code "48") (name "Net-(U14B-LED3{slash}PHYAD2{slash}GPIO2)") (class "Default")
      (node (ref "R179") (pin "1") (pinfunction "1_1") (pintype "passive"))
      (node (ref "R191") (pin "2") (pinfunction "2_2") (pintype "passive"))
      (node (ref "U14") (pin "15") (pinfunction "LED3/PHYAD2/GPIO2_15") (pintype "output"))
    )
    (net (code "49") (name "Net-(U14B-LED4{slash}PHYAD3{slash}GPIO3)") (class "Default")
      (node (ref "R183") (pin "1") (pinfunction "1_1") (pintype "passive"))
      (node (ref "R193") (pin "2") (pinfunction "2_2") (pintype "passive"))
      (node (ref "U14") (pin "14") (pinfunction "LED4/PHYAD3/GPIO3_14") (pintype "output"))
    )
    (net (code "50") (name "Net-(U14B-LED5{slash}ALLPHYAD{slash}GPIO4)") (class "Default")
      (node (ref "R182") (pin "1") (pinfunction "1_1") (pintype "passive"))
      (node (ref "R192") (pin "2") (pinfunction "2_2") (pintype "passive"))
      (node (ref "U14") (pin "13") (pinfunction "LED5/ALLPHYAD/GPIO4_13") (pintype "output"))
    )
    (net (code "51") (name "Net-(U14B-RESET_N)") (class "Default")
      (node (ref "R184") (pin "1") (pinfunction "1_1") (pintype "passive"))
      (node (ref "R185") (pin "1") (pinfunction "1_1") (pintype "passive"))
      (node (ref "U14") (pin "43") (pinfunction "RESET_N_43") (pintype "input"))
    )
    (net (code "52") (name "SHIELD") (class "Default")
      (node (ref "C161") (pin "2") (pinfunction "2_2") (pintype "passive"))
      (node (ref "J14") (pin "0") (pintype "passive"))
    )
    (net (code "53") (name "VDDAH") (class "Default")
      (node (ref "C140") (pin "1") (pinfunction "1_1") (pintype "passive"))
      (node (ref "C142") (pin "1") (pinfunction "1_1") (pintype "passive"))
      (node (ref "C144") (pin "1") (pinfunction "1_1") (pintype "passive"))
      (node (ref "FB7") (pin "2") (pinfunction "2_2") (pintype "passive"))
      (node (ref "TP6") (pin "1") (pinfunction "1_1") (pintype "passive"))
      (node (ref "U14") (pin "1") (pinfunction "VDDAH_1") (pintype "power_in"))
      (node (ref "U14") (pin "12") (pinfunction "VDDAH_12") (pintype "power_in"))
    )
    (net (code "54") (name "VDDAL") (class "Default")
      (node (ref "C148") (pin "1") (pinfunction "1_1") (pintype "passive"))
      (node (ref "C149") (pin "1") (pinfunction "1_1") (pintype "passive"))
      (node (ref "C151") (pin "1") (pinfunction "1_1") (pintype "passive"))
      (node (ref "FB8") (pin "2") (pinfunction "2_2") (pintype "passive"))
      (node (ref "FB9") (pin "1") (pinfunction "1_1") (pintype "passive"))
      (node (ref "TP7") (pin "1") (pinfunction "1_1") (pintype "passive"))
      (node (ref "U14") (pin "4") (pinfunction "VDDAL_4") (pintype "power_in"))
      (node (ref "U14") (pin "9") (pinfunction "VDDAL_9") (pintype "power_in"))
    )
    (net (code "55") (name "VDDAL_PLL") (class "Default")
      (node (ref "C155") (pin "1") (pinfunction "1_1") (pintype "passive"))
      (node (ref "C157") (pin "1") (pinfunction "1_1") (pintype "passive"))
      (node (ref "FB9") (pin "2") (pinfunction "2_2") (pintype "passive"))
      (node (ref "TP8") (pin "1") (pinfunction "1_1") (pintype "passive"))
      (node (ref "U14") (pin "47") (pinfunction "VDDAL_PLL_47") (pintype "power_in"))
    )
    (net (code "56") (name "VDD_1V1_ETH") (class "Default")
      (node (ref "C139") (pin "1") (pinfunction "1_1") (pintype "passive"))
      (node (ref "C141") (pin "1") (pinfunction "1_1") (pintype "passive"))
      (node (ref "C143") (pin "1") (pinfunction "1_1") (pintype "passive"))
      (node (ref "C145") (pin "1") (pinfunction "1_1") (pintype "passive"))
      (node (ref "C147") (pin "1") (pinfunction "1_1") (pintype "passive"))
      (node (ref "C152") (pin "2") (pinfunction "2_2") (pintype "passive"))
      (node (ref "FB8") (pin "1") (pinfunction "1_1") (pintype "passive"))
      (node (ref "R161") (pin "2") (pinfunction "2_2") (pintype "passive"))
      (node (ref "U13") (pin "12") (pinfunction "SNS_12") (pintype "input"))
      (node (ref "U13") (pin "5") (pinfunction "OUT_5") (pintype "power_in"))
      (node (ref "U13") (pin "6") (pinfunction "OUT_6") (pintype "power_in"))
      (node (ref "U13") (pin "7") (pinfunction "OUT_7") (pintype "power_in"))
      (node (ref "U14") (pin "23") (pinfunction "VDDCR_23") (pintype "power_in"))
      (node (ref "U14") (pin "27") (pinfunction "VDDCR_27") (pintype "power_in"))
      (node (ref "U14") (pin "31") (pinfunction "VDDCR_31") (pintype "power_in"))
      (node (ref "U14") (pin "40") (pinfunction "VDDCR_40") (pintype "power_in"))
    )
    (net (code "57") (name "VDD_3V3") (class "Default")
      (node (ref "C150") (pin "1") (pinfunction "1_1") (pintype "passive"))
      (node (ref "C153") (pin "1") (pinfunction "1_1") (pintype "passive"))
      (node (ref "C154") (pin "1") (pinfunction "1_1") (pintype "passive"))
      (node (ref "C156") (pin "1") (pinfunction "1_1") (pintype "passive"))
      (node (ref "C158") (pin "1") (pinfunction "1_1") (pintype "passive"))
      (node (ref "C159") (pin "1") (pinfunction "1_1") (pintype "passive"))
      (node (ref "FB7") (pin "1") (pinfunction "1_1") (pintype "passive"))
      (node (ref "J14") (pin "11") (pintype "passive"))
      (node (ref "J14") (pin "13") (pintype "passive"))
      (node (ref "R160") (pin "2") (pinfunction "2_2") (pintype "passive"))
      (node (ref "R162") (pin "2") (pinfunction "2_2") (pintype "passive"))
      (node (ref "R166") (pin "2") (pinfunction "2_2") (pintype "passive"))
      (node (ref "R167") (pin "2") (pinfunction "2_2") (pintype "passive"))
      (node (ref "R168") (pin "2") (pinfunction "2_2") (pintype "passive"))
      (node (ref "R169") (pin "2") (pinfunction "2_2") (pintype "passive"))
      (node (ref "R170") (pin "2") (pinfunction "2_2") (pintype "passive"))
      (node (ref "R171") (pin "2") (pinfunction "2_2") (pintype "passive"))
      (node (ref "R172") (pin "2") (pinfunction "2_2") (pintype "passive"))
      (node (ref "R179") (pin "2") (pinfunction "2_2") (pintype "passive"))
      (node (ref "R180") (pin "2") (pinfunction "2_2") (pintype "passive"))
      (node (ref "R181") (pin "2") (pinfunction "2_2") (pintype "passive"))
      (node (ref "R182") (pin "2") (pinfunction "2_2") (pintype "passive"))
      (node (ref "R183") (pin "2") (pinfunction "2_2") (pintype "passive"))
      (node (ref "U14") (pin "17") (pinfunction "VDDIO_17") (pintype "power_in"))
      (node (ref "U14") (pin "24") (pinfunction "VDDIO_24") (pintype "power_in"))
      (node (ref "U14") (pin "28") (pinfunction "VDDIO_28") (pintype "power_in"))
      (node (ref "U14") (pin "35") (pinfunction "VDDIO_35") (pintype "power_in"))
      (node (ref "U14") (pin "41") (pinfunction "VDDIO_41") (pintype "power_in"))
    )
    (net (code "58") (name "unconnected-(U13-SW-Pad8)") (class "Default")
      (node (ref "U13") (pin "8") (pinfunction "SW_8") (pintype "power_in+no_connect"))
    )
    (net (code "59") (name "unconnected-(U13-SW-Pad9)") (class "Default")
      (node (ref "U13") (pin "9") (pinfunction "SW_9") (pintype "power_in+no_connect"))
    )
    (net (code "60") (name "unconnected-(U13-SW-Pad10)") (class "Default")
      (node (ref "U13") (pin "10") (pinfunction "SW_10") (pintype "power_in+no_connect"))
    )
    (net (code "61") (name "unconnected-(U14A-LDO_O-Pad44)") (class "Default")
      (node (ref "U14") (pin "44") (pinfunction "LDO_O_44") (pintype "power_in+no_connect"))
    )
  )
)
